# ml_controler.net
KiCad netlist of a schematic drawn in EAGLE
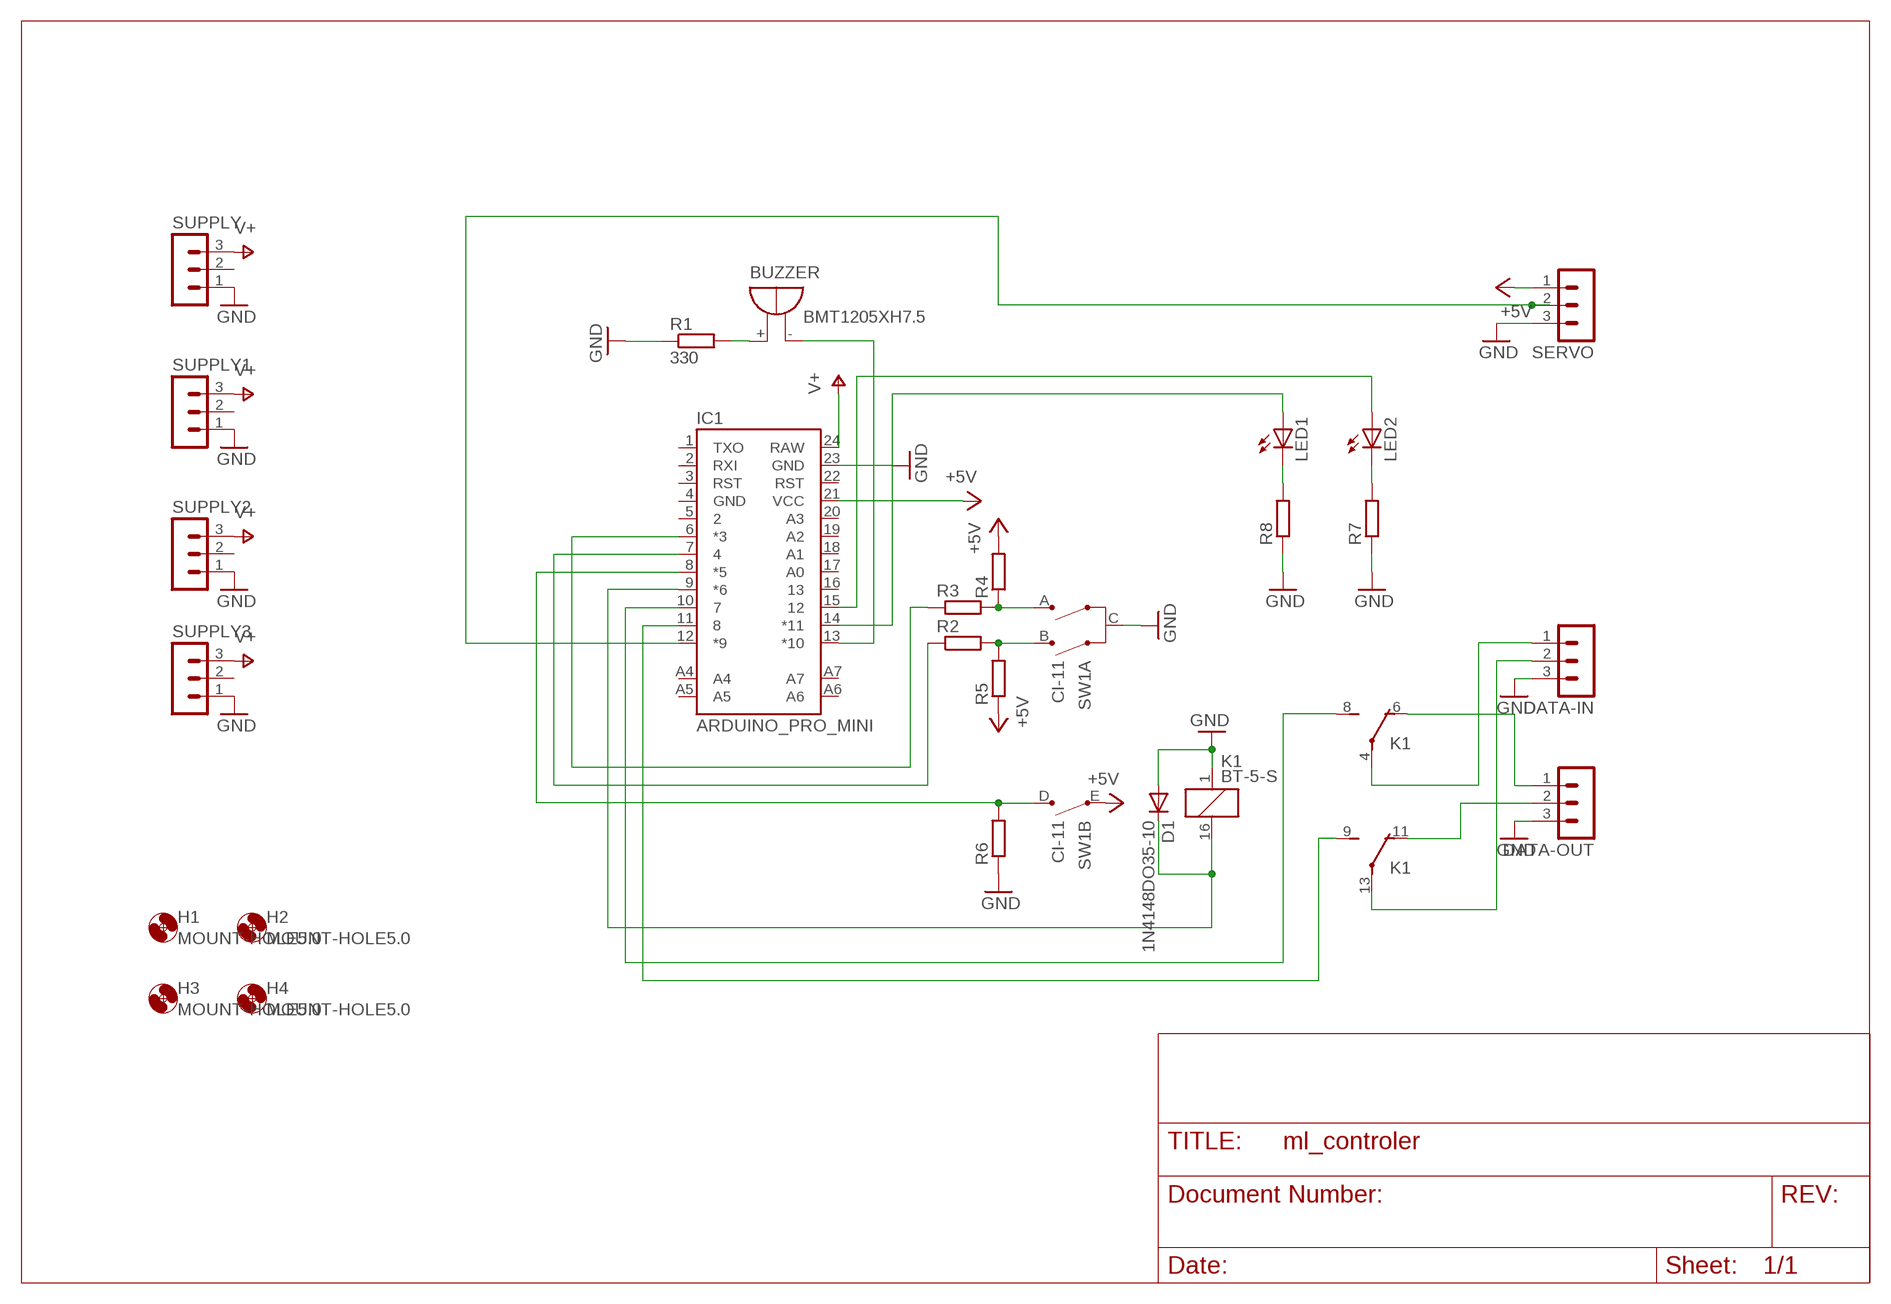
[diagram p0: schematic, sheet 1]

(export (version "E")
  (design (tool "Eeschema 10.0.6"))
  (components
    (comp (ref "BUZZER")
      (value "BMT1205XH7.5")
      (footprint "eagle-import:BMT1205XH7.5")
      (libsource (lib "eagle-import") (part "BMT1205XH7.5"))
    )
    (comp (ref "D1")
      (value "1N4148DO35-10")
      (footprint "eagle-import:DO35-10")
      (libsource (lib "eagle-import") (part "1N4148DO35-10"))
    )
    (comp (ref "DATA-IN")
      (value "MA03-1")
      (footprint "eagle-import:MA03-1")
      (libsource (lib "eagle-import") (part "MA03-1"))
    )
    (comp (ref "DATA-OUT")
      (value "MA03-1")
      (footprint "eagle-import:MA03-1")
      (libsource (lib "eagle-import") (part "MA03-1"))
    )
    (comp (ref "H1")
      (value "MOUNT-HOLE5.0")
      (footprint "eagle-import:5,0")
      (libsource (lib "eagle-import") (part "MOUNT-HOLE5.0"))
    )
    (comp (ref "H2")
      (value "MOUNT-HOLE5.0")
      (footprint "eagle-import:5,0")
      (libsource (lib "eagle-import") (part "MOUNT-HOLE5.0"))
    )
    (comp (ref "H3")
      (value "MOUNT-HOLE5.0")
      (footprint "eagle-import:5,0")
      (libsource (lib "eagle-import") (part "MOUNT-HOLE5.0"))
    )
    (comp (ref "H4")
      (value "MOUNT-HOLE5.0")
      (footprint "eagle-import:5,0")
      (libsource (lib "eagle-import") (part "MOUNT-HOLE5.0"))
    )
    (comp (ref "IC1")
      (value "ARDUINO_PRO_MINI")
      (footprint "eagle-import:ARDUINO_PRO_MINI")
      (libsource (lib "eagle-import") (part "ARDUINO_PRO_MINI"))
    )
    (comp (ref "K1")
      (value "BT-5-S")
      (footprint "eagle-import:BT-XX-S")
      (libsource (lib "eagle-import") (part "BT--S5"))
    )
    (comp (ref "LED1")
      (value "LED5MM")
      (footprint "eagle-import:LED5MM")
      (libsource (lib "eagle-import") (part "LED5MM"))
    )
    (comp (ref "LED2")
      (value "LED5MM")
      (footprint "eagle-import:LED5MM")
      (libsource (lib "eagle-import") (part "LED5MM"))
    )
    (comp (ref "R1")
      (value "330")
      (footprint "eagle-import:0207_12")
      (libsource (lib "eagle-import") (part "R-EU_0207/12"))
    )
    (comp (ref "R2")
      (value "R-EU_0207/12")
      (footprint "eagle-import:0207_12")
      (libsource (lib "eagle-import") (part "R-EU_0207/12"))
    )
    (comp (ref "R3")
      (value "R-EU_0207/12")
      (footprint "eagle-import:0207_12")
      (libsource (lib "eagle-import") (part "R-EU_0207/12"))
    )
    (comp (ref "R4")
      (value "R-EU_0207/12")
      (footprint "eagle-import:0207_12")
      (libsource (lib "eagle-import") (part "R-EU_0207/12"))
    )
    (comp (ref "R5")
      (value "R-EU_0207/12")
      (footprint "eagle-import:0207_12")
      (libsource (lib "eagle-import") (part "R-EU_0207/12"))
    )
    (comp (ref "R6")
      (value "R-EU_0207/12")
      (footprint "eagle-import:0207_12")
      (libsource (lib "eagle-import") (part "R-EU_0207/12"))
    )
    (comp (ref "R7")
      (value "R-EU_0207/12")
      (footprint "eagle-import:0207_12")
      (libsource (lib "eagle-import") (part "R-EU_0207/12"))
    )
    (comp (ref "R8")
      (value "R-EU_0207/12")
      (footprint "eagle-import:0207_12")
      (libsource (lib "eagle-import") (part "R-EU_0207/12"))
    )
    (comp (ref "SERVO")
      (value "MA03-1")
      (footprint "eagle-import:MA03-1")
      (libsource (lib "eagle-import") (part "MA03-1"))
    )
    (comp (ref "SUPPLY")
      (value "MA03-1")
      (footprint "eagle-import:MA03-1")
      (libsource (lib "eagle-import") (part "MA03-1"))
    )
    (comp (ref "SUPPLY1")
      (value "MA03-1")
      (footprint "eagle-import:MA03-1")
      (libsource (lib "eagle-import") (part "MA03-1"))
    )
    (comp (ref "SUPPLY2")
      (value "MA03-1")
      (footprint "eagle-import:MA03-1")
      (libsource (lib "eagle-import") (part "MA03-1"))
    )
    (comp (ref "SUPPLY3")
      (value "MA03-1")
      (footprint "eagle-import:MA03-1")
      (libsource (lib "eagle-import") (part "MA03-1"))
    )
    (comp (ref "SW1")
      (value "CI-11")
      (footprint "eagle-import:CI-11")
      (libsource (lib "eagle-import") (part "CI-11"))
    )
  )
  (nets
    (net (code "1") (name "+5V") (class "Default")
      (node (ref "IC1") (pin "21") (pinfunction "VCC_21") (pintype "bidirectional"))
      (node (ref "R4") (pin "2") (pinfunction "2_2") (pintype "passive"))
      (node (ref "R5") (pin "1") (pinfunction "1_1") (pintype "passive"))
      (node (ref "SERVO") (pin "1") (pinfunction "1_1") (pintype "passive"))
      (node (ref "SW1") (pin "E") (pinfunction "E_E") (pintype "passive"))
    )
    (net (code "2") (name "GND") (class "Default")
      (node (ref "D1") (pin "A") (pinfunction "A_A") (pintype "passive"))
      (node (ref "DATA-IN") (pin "3") (pinfunction "3_3") (pintype "passive"))
      (node (ref "DATA-OUT") (pin "3") (pinfunction "3_3") (pintype "passive"))
      (node (ref "IC1") (pin "23") (pinfunction "GND_23") (pintype "bidirectional"))
      (node (ref "K1") (pin "1") (pinfunction "1_1") (pintype "passive"))
      (node (ref "R1") (pin "1") (pinfunction "1_1") (pintype "passive"))
      (node (ref "R6") (pin "1") (pinfunction "1_1") (pintype "passive"))
      (node (ref "R7") (pin "1") (pinfunction "1_1") (pintype "passive"))
      (node (ref "R8") (pin "1") (pinfunction "1_1") (pintype "passive"))
      (node (ref "SERVO") (pin "3") (pinfunction "3_3") (pintype "passive"))
      (node (ref "SUPPLY") (pin "1") (pinfunction "1_1") (pintype "passive"))
      (node (ref "SUPPLY1") (pin "1") (pinfunction "1_1") (pintype "passive"))
      (node (ref "SUPPLY2") (pin "1") (pinfunction "1_1") (pintype "passive"))
      (node (ref "SUPPLY3") (pin "1") (pinfunction "1_1") (pintype "passive"))
      (node (ref "SW1") (pin "C") (pinfunction "C_C") (pintype "passive"))
    )
    (net (code "3") (name "Net-(BUZZER-Pad+)") (class "Default")
      (node (ref "BUZZER") (pin "+") (pinfunction "+_+") (pintype "passive"))
      (node (ref "R1") (pin "2") (pinfunction "2_2") (pintype "passive"))
    )
    (net (code "4") (name "Net-(IC1-*3)") (class "Default")
      (node (ref "IC1") (pin "6") (pinfunction "*3_6") (pintype "bidirectional"))
      (node (ref "R3") (pin "1") (pinfunction "1_1") (pintype "passive"))
    )
    (net (code "5") (name "Net-(IC1-*5)") (class "Default")
      (node (ref "IC1") (pin "8") (pinfunction "*5_8") (pintype "bidirectional"))
      (node (ref "R6") (pin "2") (pinfunction "2_2") (pintype "passive"))
      (node (ref "SW1") (pin "D") (pinfunction "D_D") (pintype "passive"))
    )
    (net (code "6") (name "Net-(IC1-*6)") (class "Default")
      (node (ref "D1") (pin "C") (pinfunction "C_C") (pintype "passive"))
      (node (ref "IC1") (pin "9") (pinfunction "*6_9") (pintype "bidirectional"))
      (node (ref "K1") (pin "16") (pinfunction "2_16") (pintype "passive"))
    )
    (net (code "7") (name "Net-(IC1-*9)") (class "Default")
      (node (ref "IC1") (pin "12") (pinfunction "*9_12") (pintype "bidirectional"))
      (node (ref "SERVO") (pin "2") (pinfunction "2_2") (pintype "passive"))
    )
    (net (code "8") (name "Net-(IC1-*10)") (class "Default")
      (node (ref "BUZZER") (pin "-") (pinfunction "-_-") (pintype "passive"))
      (node (ref "IC1") (pin "13") (pinfunction "*10_13") (pintype "bidirectional"))
    )
    (net (code "9") (name "Net-(IC1-*11)") (class "Default")
      (node (ref "IC1") (pin "14") (pinfunction "*11_14") (pintype "bidirectional"))
      (node (ref "LED1") (pin "A") (pinfunction "A_A") (pintype "passive"))
    )
    (net (code "10") (name "Net-(IC1-4)") (class "Default")
      (node (ref "IC1") (pin "7") (pinfunction "4_7") (pintype "bidirectional"))
      (node (ref "R2") (pin "1") (pinfunction "1_1") (pintype "passive"))
    )
    (net (code "11") (name "Net-(IC1-7)") (class "Default")
      (node (ref "IC1") (pin "10") (pinfunction "7_10") (pintype "bidirectional"))
      (node (ref "K1") (pin "8") (pinfunction "S_8") (pintype "passive"))
    )
    (net (code "12") (name "Net-(IC1-8)") (class "Default")
      (node (ref "IC1") (pin "11") (pinfunction "8_11") (pintype "bidirectional"))
      (node (ref "K1") (pin "9") (pinfunction "S_9") (pintype "passive"))
    )
    (net (code "13") (name "Net-(IC1-12)") (class "Default")
      (node (ref "IC1") (pin "15") (pinfunction "12_15") (pintype "bidirectional"))
      (node (ref "LED2") (pin "A") (pinfunction "A_A") (pintype "passive"))
    )
    (net (code "14") (name "Net-(K1A-O)") (class "Default")
      (node (ref "DATA-OUT") (pin "1") (pinfunction "1_1") (pintype "passive"))
      (node (ref "K1") (pin "6") (pinfunction "O_6") (pintype "passive"))
    )
    (net (code "15") (name "Net-(K1A-P)") (class "Default")
      (node (ref "DATA-IN") (pin "1") (pinfunction "1_1") (pintype "passive"))
      (node (ref "K1") (pin "4") (pinfunction "P_4") (pintype "passive"))
    )
    (net (code "16") (name "Net-(K1B-O)") (class "Default")
      (node (ref "DATA-OUT") (pin "2") (pinfunction "2_2") (pintype "passive"))
      (node (ref "K1") (pin "11") (pinfunction "O_11") (pintype "passive"))
    )
    (net (code "17") (name "Net-(K1B-P)") (class "Default")
      (node (ref "DATA-IN") (pin "2") (pinfunction "2_2") (pintype "passive"))
      (node (ref "K1") (pin "13") (pinfunction "P_13") (pintype "passive"))
    )
    (net (code "18") (name "Net-(LED1-C)") (class "Default")
      (node (ref "LED1") (pin "K") (pinfunction "C_K") (pintype "passive"))
      (node (ref "R8") (pin "2") (pinfunction "2_2") (pintype "passive"))
    )
    (net (code "19") (name "Net-(LED2-C)") (class "Default")
      (node (ref "LED2") (pin "K") (pinfunction "C_K") (pintype "passive"))
      (node (ref "R7") (pin "2") (pinfunction "2_2") (pintype "passive"))
    )
    (net (code "20") (name "Net-(R2-Pad2)") (class "Default")
      (node (ref "R2") (pin "2") (pinfunction "2_2") (pintype "passive"))
      (node (ref "R5") (pin "2") (pinfunction "2_2") (pintype "passive"))
      (node (ref "SW1") (pin "B") (pinfunction "B_B") (pintype "passive"))
    )
    (net (code "21") (name "Net-(R3-Pad2)") (class "Default")
      (node (ref "R3") (pin "2") (pinfunction "2_2") (pintype "passive"))
      (node (ref "R4") (pin "1") (pinfunction "1_1") (pintype "passive"))
      (node (ref "SW1") (pin "A") (pinfunction "A_A") (pintype "passive"))
    )
    (net (code "22") (name "V+") (class "Default")
      (node (ref "IC1") (pin "24") (pinfunction "RAW_24") (pintype "bidirectional"))
      (node (ref "SUPPLY") (pin "3") (pinfunction "3_3") (pintype "passive"))
      (node (ref "SUPPLY1") (pin "3") (pinfunction "3_3") (pintype "passive"))
      (node (ref "SUPPLY2") (pin "3") (pinfunction "3_3") (pintype "passive"))
      (node (ref "SUPPLY3") (pin "3") (pinfunction "3_3") (pintype "passive"))
    )
    (net (code "23") (name "unconnected-(IC1-2-Pad5)") (class "Default")
      (node (ref "IC1") (pin "5") (pinfunction "2_5") (pintype "bidirectional"))
    )
    (net (code "24") (name "unconnected-(IC1-13-Pad16)") (class "Default")
      (node (ref "IC1") (pin "16") (pinfunction "13_16") (pintype "bidirectional"))
    )
    (net (code "25") (name "unconnected-(IC1-A0-Pad17)") (class "Default")
      (node (ref "IC1") (pin "17") (pinfunction "A0_17") (pintype "bidirectional"))
    )
    (net (code "26") (name "unconnected-(IC1-A1-Pad18)") (class "Default")
      (node (ref "IC1") (pin "18") (pinfunction "A1_18") (pintype "bidirectional"))
    )
    (net (code "27") (name "unconnected-(IC1-A2-Pad19)") (class "Default")
      (node (ref "IC1") (pin "19") (pinfunction "A2_19") (pintype "bidirectional"))
    )
    (net (code "28") (name "unconnected-(IC1-A3-Pad20)") (class "Default")
      (node (ref "IC1") (pin "20") (pinfunction "A3_20") (pintype "bidirectional"))
    )
    (net (code "29") (name "unconnected-(IC1-GND-Pad4)") (class "Default")
      (node (ref "IC1") (pin "4") (pinfunction "GND_4") (pintype "bidirectional"))
    )
    (net (code "30") (name "unconnected-(IC1-PadA4)") (class "Default")
      (node (ref "IC1") (pin "A4") (pinfunction "A4_A4") (pintype "bidirectional"))
    )
    (net (code "31") (name "unconnected-(IC1-PadA5)") (class "Default")
      (node (ref "IC1") (pin "A5") (pinfunction "A5_A5") (pintype "bidirectional"))
    )
    (net (code "32") (name "unconnected-(IC1-PadA6)") (class "Default")
      (node (ref "IC1") (pin "A6") (pinfunction "A6_A6") (pintype "bidirectional"))
    )
    (net (code "33") (name "unconnected-(IC1-PadA7)") (class "Default")
      (node (ref "IC1") (pin "A7") (pinfunction "A7_A7") (pintype "bidirectional"))
    )
    (net (code "34") (name "unconnected-(IC1-RST-Pad3)") (class "Default")
      (node (ref "IC1") (pin "3") (pinfunction "RST_3") (pintype "bidirectional"))
    )
    (net (code "35") (name "unconnected-(IC1-RST-Pad22)") (class "Default")
      (node (ref "IC1") (pin "22") (pinfunction "RST_22") (pintype "bidirectional"))
    )
    (net (code "36") (name "unconnected-(IC1-RXI-Pad2)") (class "Default")
      (node (ref "IC1") (pin "2") (pinfunction "RXI_2") (pintype "bidirectional"))
    )
    (net (code "37") (name "unconnected-(IC1-TXO-Pad1)") (class "Default")
      (node (ref "IC1") (pin "1") (pinfunction "TXO_1") (pintype "bidirectional"))
    )
    (net (code "38") (name "unconnected-(SUPPLY-Pad2)") (class "Default")
      (node (ref "SUPPLY") (pin "2") (pinfunction "2_2") (pintype "passive"))
    )
    (net (code "39") (name "unconnected-(SUPPLY1-Pad2)") (class "Default")
      (node (ref "SUPPLY1") (pin "2") (pinfunction "2_2") (pintype "passive"))
    )
    (net (code "40") (name "unconnected-(SUPPLY2-Pad2)") (class "Default")
      (node (ref "SUPPLY2") (pin "2") (pinfunction "2_2") (pintype "passive"))
    )
    (net (code "41") (name "unconnected-(SUPPLY3-Pad2)") (class "Default")
      (node (ref "SUPPLY3") (pin "2") (pinfunction "2_2") (pintype "passive"))
    )
  )
)
